# cytron-1.net
KiCad netlist of a schematic drawn in EAGLE
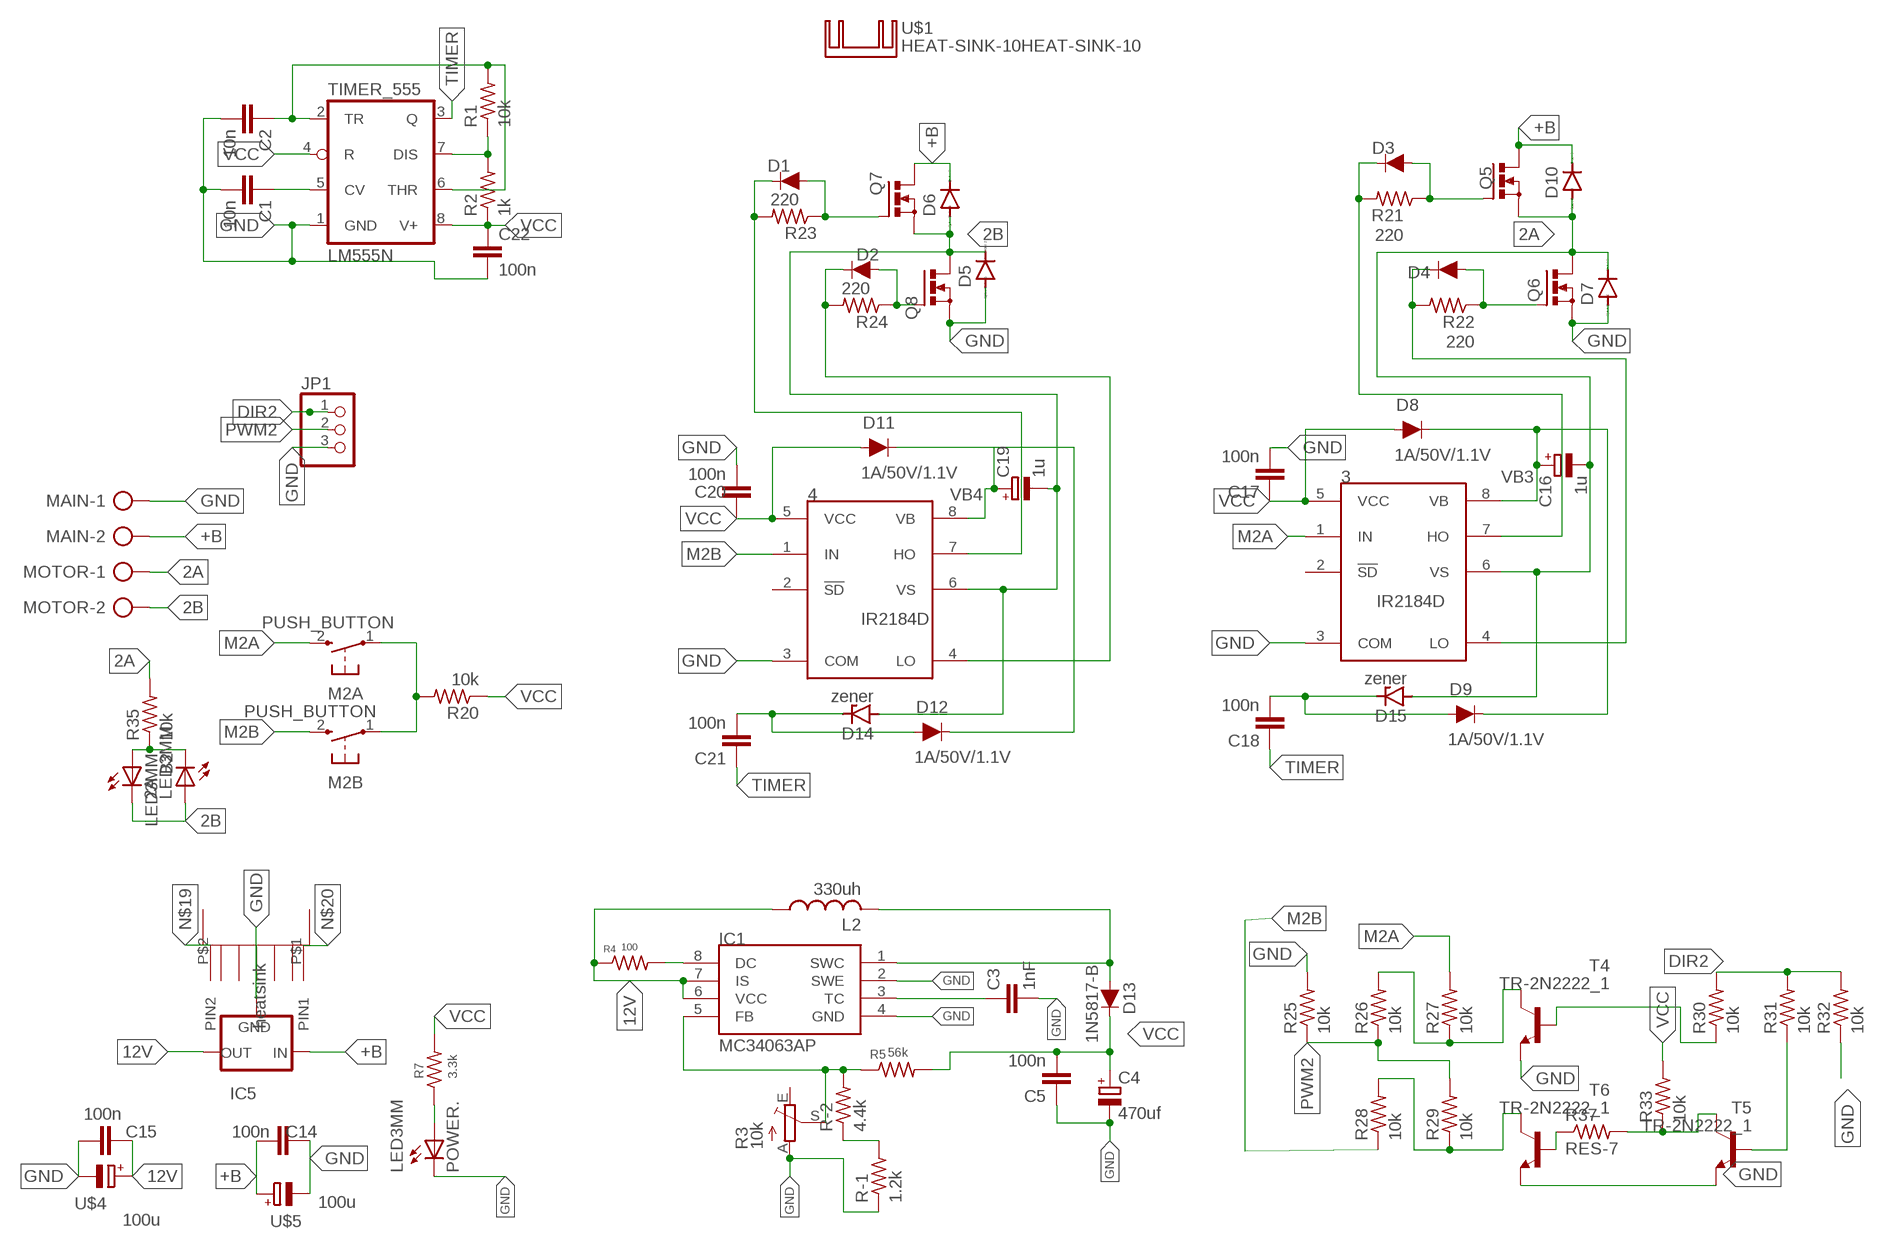
[diagram p0: schematic, sheet 1]

(export (version "E")
  (design (tool "Eeschema 10.0.6"))
  (components
    (comp (ref "2A")
      (value "LED3MM")
      (footprint "eagle-import:LED3MM")
      (libsource (lib "eagle-import") (part "LED3MM"))
    )
    (comp (ref "3")
      (value "IR2184D")
      (footprint "eagle-import:DIL08")
      (libsource (lib "eagle-import") (part "IR2184D"))
    )
    (comp (ref "4")
      (value "IR2184D")
      (footprint "eagle-import:DIL08")
      (libsource (lib "eagle-import") (part "IR2184D"))
    )
    (comp (ref "B2")
      (value "LED3MM")
      (footprint "eagle-import:LED3MM")
      (libsource (lib "eagle-import") (part "LED3MM"))
    )
    (comp (ref "C1")
      (value "10n")
      (footprint "eagle-import:C025-025X050")
      (libsource (lib "eagle-import") (part "CAPACITOR"))
    )
    (comp (ref "C2")
      (value "10n")
      (footprint "eagle-import:C025-025X050")
      (libsource (lib "eagle-import") (part "CAPACITOR"))
    )
    (comp (ref "C3")
      (value "1nF")
      (footprint "eagle-import:C025-025X050")
      (fields (field (name "SPICEPREFIX") "C"))
      (libsource (lib "eagle-import") (part "CAPACITOR"))
    )
    (comp (ref "C4")
      (value "470uf")
      (footprint "eagle-import:E3,5-8")
      (fields (field (name "SPICEPREFIX") "C"))
      (libsource (lib "eagle-import") (part "CAP_POL"))
    )
    (comp (ref "C5")
      (value "100n")
      (footprint "eagle-import:C025-025X050")
      (libsource (lib "eagle-import") (part "CAPACITOR"))
    )
    (comp (ref "C14")
      (value "100n")
      (footprint "eagle-import:C025-025X050")
      (libsource (lib "eagle-import") (part "CAPACITOR"))
    )
    (comp (ref "C15")
      (value "100n")
      (footprint "eagle-import:C025-025X050")
      (libsource (lib "eagle-import") (part "CAPACITOR"))
    )
    (comp (ref "C16")
      (value "1u")
      (footprint "eagle-import:E5-5")
      (libsource (lib "eagle-import") (part "CPOL-EUE5-5"))
    )
    (comp (ref "C17")
      (value "100n")
      (footprint "eagle-import:C025-025X050")
      (libsource (lib "eagle-import") (part "CAPACITOR"))
    )
    (comp (ref "C18")
      (value "100n")
      (footprint "eagle-import:C025-025X050")
      (libsource (lib "eagle-import") (part "CAPACITOR"))
    )
    (comp (ref "C19")
      (value "1u")
      (footprint "eagle-import:E5-5")
      (libsource (lib "eagle-import") (part "CPOL-EUE5-5"))
    )
    (comp (ref "C20")
      (value "100n")
      (footprint "eagle-import:C025-025X050")
      (libsource (lib "eagle-import") (part "CAPACITOR"))
    )
    (comp (ref "C21")
      (value "100n")
      (footprint "eagle-import:C025-025X050")
      (libsource (lib "eagle-import") (part "CAPACITOR"))
    )
    (comp (ref "C22")
      (value "100n")
      (footprint "eagle-import:C025-025X050")
      (libsource (lib "eagle-import") (part "CAPACITOR"))
    )
    (comp (ref "D1")
      (value "1A/50V/1.1V")
      (footprint "eagle-import:DIODE-1N4001")
      (libsource (lib "eagle-import") (part "DIODE(1A)-PTH"))
    )
    (comp (ref "D2")
      (value "1A/50V/1.1V")
      (footprint "eagle-import:DIODE-1N4001")
      (libsource (lib "eagle-import") (part "DIODE(1A)-PTH"))
    )
    (comp (ref "D3")
      (value "1A/50V/1.1V")
      (footprint "eagle-import:DIODE-1N4001")
      (libsource (lib "eagle-import") (part "DIODE(1A)-PTH"))
    )
    (comp (ref "D4")
      (value "1A/50V/1.1V")
      (footprint "eagle-import:DIODE-1N4001")
      (libsource (lib "eagle-import") (part "DIODE(1A)-PTH"))
    )
    (comp (ref "D5")
      (value "BY396")
      (footprint "eagle-import:DO201-15")
      (libsource (lib "eagle-import") (part "BY396"))
    )
    (comp (ref "D6")
      (value "BY396")
      (footprint "eagle-import:DO201-15")
      (libsource (lib "eagle-import") (part "BY396"))
    )
    (comp (ref "D7")
      (value "BY396")
      (footprint "eagle-import:DO201-15")
      (libsource (lib "eagle-import") (part "BY396"))
    )
    (comp (ref "D8")
      (value "1A/50V/1.1V")
      (footprint "eagle-import:DIODE-1N4001")
      (libsource (lib "eagle-import") (part "DIODE(1A)-PTH"))
    )
    (comp (ref "D9")
      (value "1A/50V/1.1V")
      (footprint "eagle-import:DIODE-1N4001")
      (libsource (lib "eagle-import") (part "DIODE(1A)-PTH"))
    )
    (comp (ref "D10")
      (value "BY396")
      (footprint "eagle-import:DO201-15")
      (libsource (lib "eagle-import") (part "BY396"))
    )
    (comp (ref "D11")
      (value "1A/50V/1.1V")
      (footprint "eagle-import:DIODE-1N4001")
      (libsource (lib "eagle-import") (part "DIODE(1A)-PTH"))
    )
    (comp (ref "D12")
      (value "1A/50V/1.1V")
      (footprint "eagle-import:DIODE-1N4001")
      (libsource (lib "eagle-import") (part "DIODE(1A)-PTH"))
    )
    (comp (ref "D13")
      (value "1N5817-B")
      (footprint "eagle-import:DIODE-1N4001")
      (fields (field (name "SPICEPREFIX") "D"))
      (libsource (lib "eagle-import") (part "DIODE(1A)-PTH"))
    )
    (comp (ref "D14")
      (value "zener")
      (footprint "eagle-import:SOD81")
      (libsource (lib "eagle-import") (part "BZD23"))
    )
    (comp (ref "D15")
      (value "zener")
      (footprint "eagle-import:SOD81")
      (libsource (lib "eagle-import") (part "BZD23"))
    )
    (comp (ref "IC1")
      (value "MC34063AP")
      (footprint "eagle-import:DIL08")
      (fields (field (name "SPICEPREFIX") "X"))
      (libsource (lib "eagle-import") (part "MC34063AP"))
    )
    (comp (ref "IC5")
      (value "78XXS")
      (footprint "eagle-import:78XXS")
      (libsource (lib "eagle-import") (part "78XXS"))
    )
    (comp (ref "JP1")
      (value "PINHD-3_DATA")
      (footprint "eagle-import:1X03_DATA")
      (libsource (lib "eagle-import") (part "PINHD-3_DATA"))
    )
    (comp (ref "L2")
      (value "330uh")
      (footprint "eagle-import:PIS2816")
      (libsource (lib "eagle-import") (part "INDUCTOR-2PIS2816"))
    )
    (comp (ref "M2A")
      (value "PUSH_BUTTON")
      (footprint "eagle-import:B3F-10XX")
      (libsource (lib "eagle-import") (part "PUSH_BUTTON"))
    )
    (comp (ref "M2B")
      (value "PUSH_BUTTON")
      (footprint "eagle-import:B3F-10XX")
      (libsource (lib "eagle-import") (part "PUSH_BUTTON"))
    )
    (comp (ref "MAIN")
      (value "ROSTA.POWER")
      (footprint "eagle-import:W239-302")
      (libsource (lib "eagle-import") (part "ROSTA.POWER"))
    )
    (comp (ref "MOTOR")
      (value "ROSTA.POWER")
      (footprint "eagle-import:W239-302")
      (libsource (lib "eagle-import") (part "ROSTA.POWER"))
    )
    (comp (ref "POWER.")
      (value "LED3MM")
      (footprint "eagle-import:LED3MM")
      (fields (field (name "SPICEPREFIX") "B"))
      (libsource (lib "eagle-import") (part "LED3MM"))
    )
    (comp (ref "Q5")
      (value "MOSFET_NTO220BV")
      (footprint "eagle-import:TO220BV")
      (libsource (lib "eagle-import") (part "MOSFET_NTO220BV"))
    )
    (comp (ref "Q6")
      (value "MOSFET_NTO220BV")
      (footprint "eagle-import:TO220BV")
      (libsource (lib "eagle-import") (part "MOSFET_NTO220BV"))
    )
    (comp (ref "Q7")
      (value "MOSFET_NTO220BV")
      (footprint "eagle-import:TO220BV")
      (libsource (lib "eagle-import") (part "MOSFET_NTO220BV"))
    )
    (comp (ref "Q8")
      (value "MOSFET_NTO220BV")
      (footprint "eagle-import:TO220BV")
      (libsource (lib "eagle-import") (part "MOSFET_NTO220BV"))
    )
    (comp (ref "R-1")
      (value "1.2k")
      (footprint "eagle-import:0204_7")
      (libsource (lib "eagle-import") (part "RES-7"))
    )
    (comp (ref "R-2")
      (value "4.4k")
      (footprint "eagle-import:0204_7")
      (libsource (lib "eagle-import") (part "RES-7"))
    )
    (comp (ref "R1")
      (value "10k")
      (footprint "eagle-import:0204_7")
      (libsource (lib "eagle-import") (part "R-US_0204/7"))
    )
    (comp (ref "R2")
      (value "1k")
      (footprint "eagle-import:0204_7")
      (libsource (lib "eagle-import") (part "R-US_0204/7"))
    )
    (comp (ref "R3")
      (value "10k")
      (footprint "eagle-import:CA6V")
      (fields (field (name "SPICEPREFIX") "J"))
      (libsource (lib "eagle-import") (part "TRIM_EU-CA6V"))
    )
    (comp (ref "R4")
      (value "100")
      (footprint "eagle-import:0204_7")
      (fields (field (name "SPICEPREFIX") "R"))
      (libsource (lib "eagle-import") (part "RES-7"))
    )
    (comp (ref "R5")
      (value "56k")
      (footprint "eagle-import:0204_7")
      (fields (field (name "SPICEPREFIX") "R"))
      (libsource (lib "eagle-import") (part "RES-7"))
    )
    (comp (ref "R7")
      (value "3.3k")
      (footprint "eagle-import:0204_7")
      (fields (field (name "SPICEPREFIX") "R"))
      (libsource (lib "eagle-import") (part "RES-7"))
    )
    (comp (ref "R20")
      (value "10k")
      (footprint "eagle-import:0204_7")
      (libsource (lib "eagle-import") (part "R-US_0204/7"))
    )
    (comp (ref "R21")
      (value "220")
      (footprint "eagle-import:0204_7")
      (libsource (lib "eagle-import") (part "R-US_0204/7"))
    )
    (comp (ref "R22")
      (value "220")
      (footprint "eagle-import:0204_7")
      (libsource (lib "eagle-import") (part "R-US_0204/7"))
    )
    (comp (ref "R23")
      (value "220")
      (footprint "eagle-import:0204_7")
      (libsource (lib "eagle-import") (part "R-US_0204/7"))
    )
    (comp (ref "R24")
      (value "220")
      (footprint "eagle-import:0204_7")
      (libsource (lib "eagle-import") (part "R-US_0204/7"))
    )
    (comp (ref "R25")
      (value "10k")
      (footprint "eagle-import:0204_7")
      (libsource (lib "eagle-import") (part "R-US_0204/7"))
    )
    (comp (ref "R26")
      (value "10k")
      (footprint "eagle-import:0204_7")
      (libsource (lib "eagle-import") (part "R-US_0204/7"))
    )
    (comp (ref "R27")
      (value "10k")
      (footprint "eagle-import:0204_7")
      (libsource (lib "eagle-import") (part "R-US_0204/7"))
    )
    (comp (ref "R28")
      (value "10k")
      (footprint "eagle-import:0204_7")
      (libsource (lib "eagle-import") (part "R-US_0204/7"))
    )
    (comp (ref "R29")
      (value "10k")
      (footprint "eagle-import:0204_7")
      (libsource (lib "eagle-import") (part "R-US_0204/7"))
    )
    (comp (ref "R30")
      (value "10k")
      (footprint "eagle-import:0204_7")
      (libsource (lib "eagle-import") (part "R-US_0204/7"))
    )
    (comp (ref "R31")
      (value "10k")
      (footprint "eagle-import:0204_7")
      (libsource (lib "eagle-import") (part "R-US_0204/7"))
    )
    (comp (ref "R32")
      (value "10k")
      (footprint "eagle-import:0204_7")
      (libsource (lib "eagle-import") (part "R-US_0204/7"))
    )
    (comp (ref "R33")
      (value "10k")
      (footprint "eagle-import:0204_7")
      (libsource (lib "eagle-import") (part "R-US_0204/7"))
    )
    (comp (ref "R35")
      (value "10k")
      (footprint "eagle-import:0204_7")
      (libsource (lib "eagle-import") (part "R-US_0204/7"))
    )
    (comp (ref "R37")
      (value "RES-7")
      (footprint "eagle-import:0204_7")
      (fields (field (name "SPICEPREFIX") "B"))
      (libsource (lib "eagle-import") (part "RES-7"))
    )
    (comp (ref "T4")
      (value "TR-2N2222_1")
      (footprint "eagle-import:TO92-EBC")
      (fields (field (name "SPICEPREFIX") "J"))
      (libsource (lib "eagle-import") (part "TR-2N2222_1"))
    )
    (comp (ref "T5")
      (value "TR-2N2222_1")
      (footprint "eagle-import:TO92-EBC")
      (fields (field (name "SPICEPREFIX") "J"))
      (libsource (lib "eagle-import") (part "TR-2N2222_1"))
    )
    (comp (ref "T6")
      (value "TR-2N2222_1")
      (footprint "eagle-import:TO92-EBC")
      (fields (field (name "SPICEPREFIX") "J"))
      (libsource (lib "eagle-import") (part "TR-2N2222_1"))
    )
    (comp (ref "TIMER_555")
      (value "LM555N")
      (footprint "eagle-import:DIL08")
      (libsource (lib "eagle-import") (part "555NLM"))
    )
    (comp (ref "U$1")
      (value "HEAT-SINK-10HEAT-SINK-10")
      (footprint "eagle-import:HS10")
      (libsource (lib "eagle-import") (part "HEAT-SINK-10HEAT-SINK-10"))
    )
    (comp (ref "U$3")
      (value "HEAT-SINK")
      (footprint "eagle-import:HEAT_SINK")
      (libsource (lib "eagle-import") (part "HEAT-SINK"))
    )
    (comp (ref "U$4")
      (value "100u")
      (footprint "eagle-import:E3,5-8")
      (libsource (lib "eagle-import") (part "CAP_POL"))
    )
    (comp (ref "U$5")
      (value "100u")
      (footprint "eagle-import:E3,5-8")
      (libsource (lib "eagle-import") (part "CAP_POL"))
    )
  )
  (nets
    (net (code "1") (name "+B") (class "Default")
      (node (ref "C14") (pin "1") (pinfunction "1_1") (pintype "passive"))
      (node (ref "D10") (pin "C") (pinfunction "C_C") (pintype "passive"))
      (node (ref "D6") (pin "C") (pinfunction "C_C") (pintype "passive"))
      (node (ref "IC5") (pin "IN") (pinfunction "IN_IN") (pintype "input"))
      (node (ref "MAIN") (pin "2") (pinfunction "KL_2") (pintype "passive"))
      (node (ref "Q5") (pin "D") (pinfunction "D_D") (pintype "passive"))
      (node (ref "Q7") (pin "D") (pinfunction "D_D") (pintype "passive"))
      (node (ref "U$5") (pin "+") (pinfunction "+_+") (pintype "passive"))
    )
    (net (code "2") (name "/VB3") (class "Default")
      (node (ref "3") (pin "8") (pinfunction "VB_8") (pintype "power_in"))
      (node (ref "C16") (pin "+") (pinfunction "+_+") (pintype "passive"))
      (node (ref "D8") (pin "C") (pinfunction "C_C") (pintype "passive"))
      (node (ref "D9") (pin "C") (pinfunction "C_C") (pintype "passive"))
    )
    (net (code "3") (name "/VB4") (class "Default")
      (node (ref "4") (pin "8") (pinfunction "VB_8") (pintype "power_in"))
      (node (ref "C19") (pin "+") (pinfunction "+_+") (pintype "passive"))
      (node (ref "D11") (pin "C") (pinfunction "C_C") (pintype "passive"))
      (node (ref "D12") (pin "C") (pinfunction "C_C") (pintype "passive"))
    )
    (net (code "4") (name "2A") (class "Default")
      (node (ref "3") (pin "6") (pinfunction "VS_6") (pintype "power_in"))
      (node (ref "C16") (pin "-") (pinfunction "-_-") (pintype "passive"))
      (node (ref "D10") (pin "A") (pinfunction "A_A") (pintype "passive"))
      (node (ref "D15") (pin "A") (pinfunction "A_A") (pintype "passive"))
      (node (ref "D7") (pin "C") (pinfunction "C_C") (pintype "passive"))
      (node (ref "MOTOR") (pin "1") (pinfunction "KL_1") (pintype "passive"))
      (node (ref "Q5") (pin "S") (pinfunction "S_S") (pintype "passive"))
      (node (ref "Q6") (pin "D") (pinfunction "D_D") (pintype "passive"))
      (node (ref "R35") (pin "2") (pinfunction "2_2") (pintype "passive"))
    )
    (net (code "5") (name "2B") (class "Default")
      (node (ref "2A") (pin "K") (pinfunction "C_K") (pintype "passive"))
      (node (ref "4") (pin "6") (pinfunction "VS_6") (pintype "power_in"))
      (node (ref "B2") (pin "A") (pinfunction "A_A") (pintype "passive"))
      (node (ref "C19") (pin "-") (pinfunction "-_-") (pintype "passive"))
      (node (ref "D14") (pin "A") (pinfunction "A_A") (pintype "passive"))
      (node (ref "D5") (pin "C") (pinfunction "C_C") (pintype "passive"))
      (node (ref "D6") (pin "A") (pinfunction "A_A") (pintype "passive"))
      (node (ref "MOTOR") (pin "2") (pinfunction "KL_2") (pintype "passive"))
      (node (ref "Q7") (pin "S") (pinfunction "S_S") (pintype "passive"))
      (node (ref "Q8") (pin "D") (pinfunction "D_D") (pintype "passive"))
    )
    (net (code "6") (name "12V") (class "Default")
      (node (ref "C15") (pin "2") (pinfunction "2_2") (pintype "passive"))
      (node (ref "IC1") (pin "6") (pinfunction "VCC_6") (pintype "passive"))
      (node (ref "IC1") (pin "7") (pinfunction "IS_7") (pintype "passive"))
      (node (ref "IC5") (pin "OUT") (pinfunction "OUT_OUT") (pintype "passive"))
      (node (ref "L2") (pin "1") (pinfunction "1_1") (pintype "passive"))
      (node (ref "R4") (pin "1") (pinfunction "1_1") (pintype "passive"))
      (node (ref "U$4") (pin "+") (pinfunction "+_+") (pintype "passive"))
    )
    (net (code "7") (name "DIR2") (class "Default")
      (node (ref "JP1") (pin "1") (pinfunction "1_1") (pintype "passive"))
      (node (ref "R30") (pin "2") (pinfunction "2_2") (pintype "passive"))
      (node (ref "R31") (pin "2") (pinfunction "2_2") (pintype "passive"))
      (node (ref "R32") (pin "2") (pinfunction "2_2") (pintype "passive"))
    )
    (net (code "8") (name "GND") (class "Default")
      (node (ref "3") (pin "3") (pinfunction "COM_3") (pintype "power_in"))
      (node (ref "4") (pin "3") (pinfunction "COM_3") (pintype "power_in"))
      (node (ref "C1") (pin "2") (pinfunction "2_2") (pintype "passive"))
      (node (ref "C14") (pin "2") (pinfunction "2_2") (pintype "passive"))
      (node (ref "C15") (pin "1") (pinfunction "1_1") (pintype "passive"))
      (node (ref "C17") (pin "2") (pinfunction "2_2") (pintype "passive"))
      (node (ref "C2") (pin "2") (pinfunction "2_2") (pintype "passive"))
      (node (ref "C20") (pin "2") (pinfunction "2_2") (pintype "passive"))
      (node (ref "C22") (pin "2") (pinfunction "2_2") (pintype "passive"))
      (node (ref "C3") (pin "2") (pinfunction "2_2") (pintype "passive"))
      (node (ref "C4") (pin "-") (pinfunction "-_-") (pintype "passive"))
      (node (ref "C5") (pin "1") (pinfunction "1_1") (pintype "passive"))
      (node (ref "D5") (pin "A") (pinfunction "A_A") (pintype "passive"))
      (node (ref "D7") (pin "A") (pinfunction "A_A") (pintype "passive"))
      (node (ref "IC1") (pin "2") (pinfunction "SWE_2") (pintype "passive"))
      (node (ref "IC1") (pin "4") (pinfunction "GND_4") (pintype "passive"))
      (node (ref "IC5") (pin "GND") (pinfunction "GND_GND") (pintype "input"))
      (node (ref "JP1") (pin "3") (pinfunction "3_3") (pintype "passive"))
      (node (ref "MAIN") (pin "1") (pinfunction "KL_1") (pintype "passive"))
      (node (ref "POWER.") (pin "K") (pinfunction "C_K") (pintype "passive"))
      (node (ref "Q6") (pin "S") (pinfunction "S_S") (pintype "passive"))
      (node (ref "Q8") (pin "S") (pinfunction "S_S") (pintype "passive"))
      (node (ref "R-1") (pin "1") (pinfunction "1_1") (pintype "passive"))
      (node (ref "R25") (pin "2") (pinfunction "2_2") (pintype "passive"))
      (node (ref "R3") (pin "A") (pinfunction "A_A") (pintype "passive"))
      (node (ref "R32") (pin "1") (pinfunction "1_1") (pintype "passive"))
      (node (ref "T4") (pin "E") (pinfunction "E_E") (pintype "passive"))
      (node (ref "T5") (pin "E") (pinfunction "E_E") (pintype "passive"))
      (node (ref "T6") (pin "E") (pinfunction "E_E") (pintype "passive"))
      (node (ref "TIMER_555") (pin "1") (pinfunction "GND_1") (pintype "power_in"))
      (node (ref "U$4") (pin "-") (pinfunction "-_-") (pintype "passive"))
      (node (ref "U$5") (pin "-") (pinfunction "-_-") (pintype "passive"))
    )
    (net (code "9") (name "M2A") (class "Default")
      (node (ref "3") (pin "1") (pinfunction "IN_1") (pintype "input"))
      (node (ref "M2A") (pin "2") (pinfunction "S_2") (pintype "passive"))
      (node (ref "R27") (pin "2") (pinfunction "2_2") (pintype "passive"))
    )
    (net (code "10") (name "M2B") (class "Default")
      (node (ref "4") (pin "1") (pinfunction "IN_1") (pintype "input"))
      (node (ref "M2B") (pin "2") (pinfunction "S_2") (pintype "passive"))
      (node (ref "R28") (pin "1") (pinfunction "1_1") (pintype "passive"))
    )
    (net (code "11") (name "N$19") (class "Default")
      (node (ref "U$3") (pin "P$2") (pinfunction "PIN2_P$2") (pintype "bidirectional"))
    )
    (net (code "12") (name "N$20") (class "Default")
      (node (ref "U$3") (pin "P$1") (pinfunction "PIN1_P$1") (pintype "bidirectional"))
    )
    (net (code "13") (name "Net-(3-HO)") (class "Default")
      (node (ref "3") (pin "7") (pinfunction "HO_7") (pintype "output"))
      (node (ref "D3") (pin "C") (pinfunction "C_C") (pintype "passive"))
      (node (ref "R21") (pin "2") (pinfunction "2_2") (pintype "passive"))
    )
    (net (code "14") (name "Net-(3-LO)") (class "Default")
      (node (ref "3") (pin "4") (pinfunction "LO_4") (pintype "output"))
      (node (ref "D4") (pin "C") (pinfunction "C_C") (pintype "passive"))
      (node (ref "R22") (pin "2") (pinfunction "2_2") (pintype "passive"))
    )
    (net (code "15") (name "Net-(4-HO)") (class "Default")
      (node (ref "4") (pin "7") (pinfunction "HO_7") (pintype "output"))
      (node (ref "D1") (pin "C") (pinfunction "C_C") (pintype "passive"))
      (node (ref "R23") (pin "2") (pinfunction "2_2") (pintype "passive"))
    )
    (net (code "16") (name "Net-(4-LO)") (class "Default")
      (node (ref "4") (pin "4") (pinfunction "LO_4") (pintype "output"))
      (node (ref "D2") (pin "C") (pinfunction "C_C") (pintype "passive"))
      (node (ref "R24") (pin "2") (pinfunction "2_2") (pintype "passive"))
    )
    (net (code "17") (name "Net-(B2-C)") (class "Default")
      (node (ref "2A") (pin "A") (pinfunction "A_A") (pintype "passive"))
      (node (ref "B2") (pin "K") (pinfunction "C_K") (pintype "passive"))
      (node (ref "R35") (pin "1") (pinfunction "1_1") (pintype "passive"))
    )
    (net (code "18") (name "Net-(C18-Pad2)") (class "Default")
      (node (ref "C18") (pin "2") (pinfunction "2_2") (pintype "passive"))
      (node (ref "D15") (pin "C") (pinfunction "C_C") (pintype "passive"))
      (node (ref "D9") (pin "A") (pinfunction "A_A") (pintype "passive"))
    )
    (net (code "19") (name "Net-(C21-Pad2)") (class "Default")
      (node (ref "C21") (pin "2") (pinfunction "2_2") (pintype "passive"))
      (node (ref "D12") (pin "A") (pinfunction "A_A") (pintype "passive"))
      (node (ref "D14") (pin "C") (pinfunction "C_C") (pintype "passive"))
    )
    (net (code "20") (name "Net-(D1-PadA)") (class "Default")
      (node (ref "D1") (pin "A") (pinfunction "A_A") (pintype "passive"))
      (node (ref "Q7") (pin "G") (pinfunction "G_G") (pintype "passive"))
      (node (ref "R23") (pin "1") (pinfunction "1_1") (pintype "passive"))
    )
    (net (code "21") (name "Net-(D2-PadA)") (class "Default")
      (node (ref "D2") (pin "A") (pinfunction "A_A") (pintype "passive"))
      (node (ref "Q8") (pin "G") (pinfunction "G_G") (pintype "passive"))
      (node (ref "R24") (pin "1") (pinfunction "1_1") (pintype "passive"))
    )
    (net (code "22") (name "Net-(D3-PadA)") (class "Default")
      (node (ref "D3") (pin "A") (pinfunction "A_A") (pintype "passive"))
      (node (ref "Q5") (pin "G") (pinfunction "G_G") (pintype "passive"))
      (node (ref "R21") (pin "1") (pinfunction "1_1") (pintype "passive"))
    )
    (net (code "23") (name "Net-(D4-PadA)") (class "Default")
      (node (ref "D4") (pin "A") (pinfunction "A_A") (pintype "passive"))
      (node (ref "Q6") (pin "G") (pinfunction "G_G") (pintype "passive"))
      (node (ref "R22") (pin "1") (pinfunction "1_1") (pintype "passive"))
    )
    (net (code "24") (name "Net-(IC1-DC)") (class "Default")
      (node (ref "IC1") (pin "8") (pinfunction "DC_8") (pintype "passive"))
      (node (ref "R4") (pin "2") (pinfunction "2_2") (pintype "passive"))
    )
    (net (code "25") (name "Net-(IC1-FB)") (class "Default")
      (node (ref "IC1") (pin "5") (pinfunction "FB_5") (pintype "passive"))
      (node (ref "R-2") (pin "2") (pinfunction "2_2") (pintype "passive"))
      (node (ref "R3") (pin "S") (pinfunction "S_S") (pintype "passive"))
      (node (ref "R5") (pin "1") (pinfunction "1_1") (pintype "passive"))
    )
    (net (code "26") (name "Net-(IC1-SWC)") (class "Default")
      (node (ref "D13") (pin "A") (pinfunction "A_A") (pintype "passive"))
      (node (ref "IC1") (pin "1") (pinfunction "SWC_1") (pintype "passive"))
      (node (ref "L2") (pin "2") (pinfunction "2_2") (pintype "passive"))
    )
    (net (code "27") (name "Net-(IC1-TC)") (class "Default")
      (node (ref "C3") (pin "1") (pinfunction "1_1") (pintype "passive"))
      (node (ref "IC1") (pin "3") (pinfunction "TC_3") (pintype "passive"))
    )
    (net (code "28") (name "Net-(M2A-P)") (class "Default")
      (node (ref "M2A") (pin "1") (pinfunction "P_1") (pintype "passive"))
      (node (ref "M2B") (pin "1") (pinfunction "P_1") (pintype "passive"))
      (node (ref "R20") (pin "2") (pinfunction "2_2") (pintype "passive"))
    )
    (net (code "29") (name "Net-(POWER.-PadA)") (class "Default")
      (node (ref "POWER.") (pin "A") (pinfunction "A_A") (pintype "passive"))
      (node (ref "R7") (pin "1") (pinfunction "1_1") (pintype "passive"))
    )
    (net (code "30") (name "Net-(R-1-Pad2)") (class "Default")
      (node (ref "R-1") (pin "2") (pinfunction "2_2") (pintype "passive"))
      (node (ref "R-2") (pin "1") (pinfunction "1_1") (pintype "passive"))
    )
    (net (code "31") (name "Net-(R26-Pad2)") (class "Default")
      (node (ref "R26") (pin "2") (pinfunction "2_2") (pintype "passive"))
      (node (ref "R27") (pin "1") (pinfunction "1_1") (pintype "passive"))
      (node (ref "T4") (pin "C") (pinfunction "C_C") (pintype "passive"))
    )
    (net (code "32") (name "Net-(R28-Pad2)") (class "Default")
      (node (ref "R28") (pin "2") (pinfunction "2_2") (pintype "passive"))
      (node (ref "R29") (pin "1") (pinfunction "1_1") (pintype "passive"))
      (node (ref "T6") (pin "C") (pinfunction "C_C") (pintype "passive"))
    )
    (net (code "33") (name "Net-(R30-Pad1)") (class "Default")
      (node (ref "R30") (pin "1") (pinfunction "1_1") (pintype "passive"))
      (node (ref "T4") (pin "B") (pinfunction "B_B") (pintype "passive"))
    )
    (net (code "34") (name "Net-(R31-Pad1)") (class "Default")
      (node (ref "R31") (pin "1") (pinfunction "1_1") (pintype "passive"))
      (node (ref "T5") (pin "B") (pinfunction "B_B") (pintype "passive"))
    )
    (net (code "35") (name "Net-(R33-Pad1)") (class "Default")
      (node (ref "R33") (pin "1") (pinfunction "1_1") (pintype "passive"))
      (node (ref "R37") (pin "2") (pinfunction "2_2") (pintype "passive"))
      (node (ref "T5") (pin "C") (pinfunction "C_C") (pintype "passive"))
    )
    (net (code "36") (name "Net-(R37-Pad1)") (class "Default")
      (node (ref "R37") (pin "1") (pinfunction "1_1") (pintype "passive"))
      (node (ref "T6") (pin "B") (pinfunction "B_B") (pintype "passive"))
    )
    (net (code "37") (name "Net-(TIMER_555-CV)") (class "Default")
      (node (ref "C1") (pin "1") (pinfunction "1_1") (pintype "passive"))
      (node (ref "TIMER_555") (pin "5") (pinfunction "CV_5") (pintype "input"))
    )
    (net (code "38") (name "Net-(TIMER_555-DIS)") (class "Default")
      (node (ref "R1") (pin "1") (pinfunction "1_1") (pintype "passive"))
      (node (ref "R2") (pin "2") (pinfunction "2_2") (pintype "passive"))
      (node (ref "TIMER_555") (pin "7") (pinfunction "DIS_7") (pintype "input"))
    )
    (net (code "39") (name "Net-(TIMER_555-THR)") (class "Default")
      (node (ref "C2") (pin "1") (pinfunction "1_1") (pintype "passive"))
      (node (ref "R1") (pin "2") (pinfunction "2_2") (pintype "passive"))
      (node (ref "TIMER_555") (pin "2") (pinfunction "TR_2") (pintype "input"))
      (node (ref "TIMER_555") (pin "6") (pinfunction "THR_6") (pintype "input"))
    )
    (net (code "40") (name "PWM2") (class "Default")
      (node (ref "JP1") (pin "2") (pinfunction "2_2") (pintype "passive"))
      (node (ref "R25") (pin "1") (pinfunction "1_1") (pintype "passive"))
      (node (ref "R26") (pin "1") (pinfunction "1_1") (pintype "passive"))
      (node (ref "R29") (pin "2") (pinfunction "2_2") (pintype "passive"))
    )
    (net (code "41") (name "TIMER") (class "Default")
      (node (ref "C18") (pin "1") (pinfunction "1_1") (pintype "passive"))
      (node (ref "C21") (pin "1") (pinfunction "1_1") (pintype "passive"))
      (node (ref "TIMER_555") (pin "3") (pinfunction "Q_3") (pintype "output"))
    )
    (net (code "42") (name "VCC") (class "Default")
      (node (ref "3") (pin "5") (pinfunction "VCC_5") (pintype "power_in"))
      (node (ref "4") (pin "5") (pinfunction "VCC_5") (pintype "power_in"))
      (node (ref "C17") (pin "1") (pinfunction "1_1") (pintype "passive"))
      (node (ref "C20") (pin "1") (pinfunction "1_1") (pintype "passive"))
      (node (ref "C22") (pin "1") (pinfunction "1_1") (pintype "passive"))
      (node (ref "C4") (pin "+") (pinfunction "+_+") (pintype "passive"))
      (node (ref "C5") (pin "2") (pinfunction "2_2") (pintype "passive"))
      (node (ref "D11") (pin "A") (pinfunction "A_A") (pintype "passive"))
      (node (ref "D13") (pin "C") (pinfunction "C_C") (pintype "passive"))
      (node (ref "D8") (pin "A") (pinfunction "A_A") (pintype "passive"))
      (node (ref "R2") (pin "1") (pinfunction "1_1") (pintype "passive"))
      (node (ref "R20") (pin "1") (pinfunction "1_1") (pintype "passive"))
      (node (ref "R33") (pin "2") (pinfunction "2_2") (pintype "passive"))
      (node (ref "R5") (pin "2") (pinfunction "2_2") (pintype "passive"))
      (node (ref "R7") (pin "2") (pinfunction "2_2") (pintype "passive"))
      (node (ref "TIMER_555") (pin "4") (pinfunction "R_4") (pintype "input"))
      (node (ref "TIMER_555") (pin "8") (pinfunction "V+_8") (pintype "power_in"))
    )
    (net (code "43") (name "unconnected-(3-~{SD}-Pad2)") (class "Default")
      (node (ref "3") (pin "2") (pinfunction "~{SD}_2") (pintype "input"))
    )
    (net (code "44") (name "unconnected-(4-~{SD}-Pad2)") (class "Default")
      (node (ref "4") (pin "2") (pinfunction "~{SD}_2") (pintype "input"))
    )
    (net (code "45") (name "unconnected-(R3-PadE)") (class "Default")
      (node (ref "R3") (pin "E") (pinfunction "E_E") (pintype "passive"))
    )
  )
)
